# Top_Sheet.net
KiCad netlist of a schematic drawn in Altium Designer
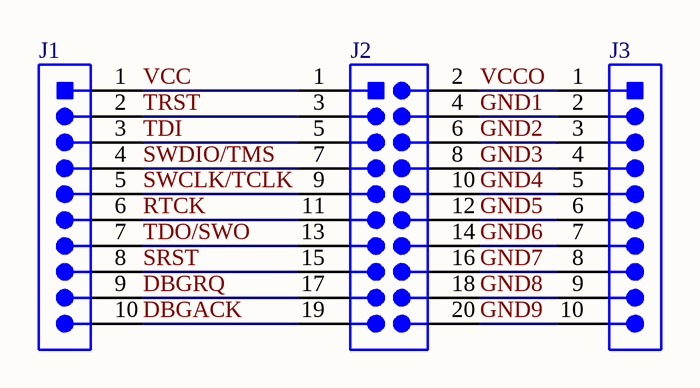
[diagram p0: Top Sheet.SchDoc]

(export (version "E")
  (design (tool "Eeschema 10.0.6"))
  (components
    (comp (ref "J1")
      (value "10 contacts Male header")
      (footprint "10129380-910001ALF")
      (description "Connector Male Header 1X10 vertical 10contacts 0.100in pitch Gold finish SMD")
      (fields (field (name "MANUFACTURER") "FCI"))
      (libsource (lib "Connectors") (part "Header 1X10"))
    )
    (comp (ref "J2")
      (value "Arm® JTAG 20 connector")
      (footprint "3020-20-0300-00 PLUGMID")
      (description "20 Pin Shrouded Header, 0.100\" SMD")
      (fields (field (name "MANUFACTURER") "CNC Tech"))
      (libsource (lib "Connectors") (part "ARM Standard JTAG"))
    )
    (comp (ref "J3")
      (value "10 contacts Male header")
      (footprint "10129380-910001ALF")
      (description "Connector Male Header 1X10 vertical 10contacts 0.100in pitch Gold finish SMD")
      (fields (field (name "MANUFACTURER") "FCI"))
      (libsource (lib "") (part "Header 1X10_1"))
    )
  )
  (nets
    (net (code "1") (name "/DBGACK") (class "Default")
      (node (ref "J1") (pin "10") (pinfunction "10_10") (pintype "passive"))
      (node (ref "J2") (pin "19") (pinfunction "DBGACK_or_VCC_IN_19") (pintype "passive"))
    )
    (net (code "2") (name "/DBGRQ") (class "Default")
      (node (ref "J1") (pin "9") (pinfunction "9_9") (pintype "passive"))
      (node (ref "J2") (pin "17") (pinfunction "DBGRQ_17") (pintype "passive"))
    )
    (net (code "3") (name "/GND1") (class "Default")
      (node (ref "J2") (pin "4") (pinfunction "4_4") (pintype "power_in"))
      (node (ref "J3") (pin "2") (pinfunction "2_2") (pintype "passive"))
    )
    (net (code "4") (name "/GND2") (class "Default")
      (node (ref "J2") (pin "6") (pinfunction "6_6") (pintype "power_in"))
      (node (ref "J3") (pin "3") (pinfunction "3_3") (pintype "passive"))
    )
    (net (code "5") (name "/GND3") (class "Default")
      (node (ref "J2") (pin "8") (pinfunction "8_8") (pintype "power_in"))
      (node (ref "J3") (pin "4") (pinfunction "4_4") (pintype "passive"))
    )
    (net (code "6") (name "/GND4") (class "Default")
      (node (ref "J2") (pin "10") (pinfunction "10_10") (pintype "power_in"))
      (node (ref "J3") (pin "5") (pinfunction "5_5") (pintype "passive"))
    )
    (net (code "7") (name "/GND5") (class "Default")
      (node (ref "J2") (pin "12") (pinfunction "12_12") (pintype "power_in"))
      (node (ref "J3") (pin "6") (pinfunction "6_6") (pintype "passive"))
    )
    (net (code "8") (name "/GND6") (class "Default")
      (node (ref "J2") (pin "14") (pinfunction "14_14") (pintype "power_in"))
      (node (ref "J3") (pin "7") (pinfunction "7_7") (pintype "passive"))
    )
    (net (code "9") (name "/GND7") (class "Default")
      (node (ref "J2") (pin "16") (pinfunction "16_16") (pintype "power_in"))
      (node (ref "J3") (pin "8") (pinfunction "8_8") (pintype "passive"))
    )
    (net (code "10") (name "/GND8") (class "Default")
      (node (ref "J2") (pin "18") (pinfunction "18_18") (pintype "power_in"))
      (node (ref "J3") (pin "9") (pinfunction "9_9") (pintype "passive"))
    )
    (net (code "11") (name "/GND9") (class "Default")
      (node (ref "J2") (pin "20") (pinfunction "20_20") (pintype "power_in"))
      (node (ref "J3") (pin "10") (pinfunction "10_10") (pintype "passive"))
    )
    (net (code "12") (name "/RTCK") (class "Default")
      (node (ref "J1") (pin "6") (pinfunction "6_6") (pintype "passive"))
      (node (ref "J2") (pin "11") (pinfunction "RTCK_11") (pintype "passive"))
    )
    (net (code "13") (name "/SRST") (class "Default")
      (node (ref "J1") (pin "8") (pinfunction "8_8") (pintype "passive"))
      (node (ref "J2") (pin "15") (pinfunction "SRST_15") (pintype "passive"))
    )
    (net (code "14") (name "/SWCLK{slash}TCLK") (class "Default")
      (node (ref "J1") (pin "5") (pinfunction "5_5") (pintype "passive"))
      (node (ref "J2") (pin "9") (pinfunction "TCK/SWCLK_9") (pintype "passive"))
    )
    (net (code "15") (name "/SWDIO{slash}TMS") (class "Default")
      (node (ref "J1") (pin "4") (pinfunction "4_4") (pintype "passive"))
      (node (ref "J2") (pin "7") (pinfunction "TMS/SWDIO_7") (pintype "passive"))
    )
    (net (code "16") (name "/TDI") (class "Default")
      (node (ref "J1") (pin "3") (pinfunction "3_3") (pintype "passive"))
      (node (ref "J2") (pin "5") (pinfunction "TDI_5") (pintype "passive"))
    )
    (net (code "17") (name "/TDO{slash}SWO") (class "Default")
      (node (ref "J1") (pin "7") (pinfunction "7_7") (pintype "passive"))
      (node (ref "J2") (pin "13") (pinfunction "TDO/SWO_13") (pintype "passive"))
    )
    (net (code "18") (name "/TRST") (class "Default")
      (node (ref "J1") (pin "2") (pinfunction "2_2") (pintype "passive"))
      (node (ref "J2") (pin "3") (pinfunction "TRST_3") (pintype "passive"))
    )
    (net (code "19") (name "/VCC") (class "Default")
      (node (ref "J1") (pin "1") (pinfunction "1_1") (pintype "passive"))
      (node (ref "J2") (pin "1") (pinfunction "VCC_Tgt_1") (pintype "power_in"))
    )
    (net (code "20") (name "/VCCO") (class "Default")
      (node (ref "J2") (pin "2") (pinfunction "VCC_(Opt)_2") (pintype "power_in"))
      (node (ref "J3") (pin "1") (pinfunction "1_1") (pintype "passive"))
    )
  )
)
